# USR_IO_IPMI.net
KiCad netlist of a schematic drawn in Altium Designer
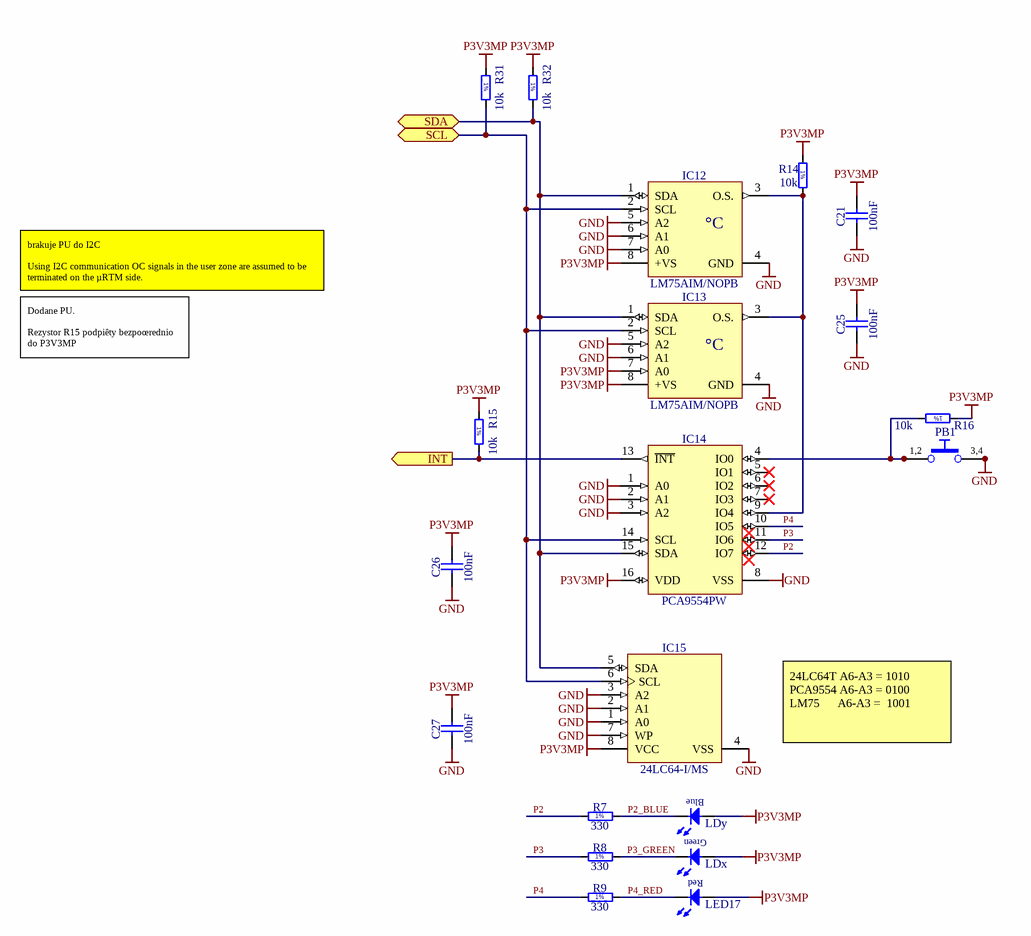
[diagram p0: USR_IO_IPMI.SchDoc]

(export (version "E")
  (design (tool "Eeschema 10.0.6"))
  (components
    (comp (ref "C21")
      (value "100nF")
      (footprint "CAPC1005X55N")
      (description "Non-polarised capacitor")
      (fields
        (field (name "PART NUMBER") "CC0402_100NF_16V_10%_X7R")
        (field (name "VOLTAGE") "16V")
        (field (name "AUTHOR") "CERN DEM JLC")
      )
      (libsource (lib "Capacitors") (part "Capacitor - non polarized"))
    )
    (comp (ref "C25")
      (value "100nF")
      (footprint "CAPC1005X55N")
      (description "Non-polarised capacitor")
      (fields
        (field (name "PART NUMBER") "CC0402_100NF_16V_10%_X7R")
        (field (name "VOLTAGE") "16V")
        (field (name "AUTHOR") "CERN DEM JLC")
      )
      (libsource (lib "Capacitors") (part "Capacitor - non polarized"))
    )
    (comp (ref "C26")
      (value "100nF")
      (footprint "CAPC1005X55N")
      (description "Non-polarised capacitor")
      (fields
        (field (name "PART NUMBER") "CC0402_100NF_16V_10%_X7R")
        (field (name "VOLTAGE") "16V")
        (field (name "AUTHOR") "CERN DEM JLC")
      )
      (libsource (lib "Capacitors") (part "Capacitor - non polarized"))
    )
    (comp (ref "C27")
      (value "100nF")
      (footprint "CAPC1005X55N")
      (description "Non-polarised capacitor")
      (fields
        (field (name "PART NUMBER") "CC0402_100NF_16V_10%_X7R")
        (field (name "VOLTAGE") "16V")
        (field (name "AUTHOR") "CERN DEM JLC")
      )
      (libsource (lib "Capacitors") (part "Capacitor - non polarized"))
    )
    (comp (ref "IC12")
      (value "LM75AIM/NOPB")
      (footprint "SOIC127P600X175-8N")
      (description "Digital Temperature Sensor and Thermal Watchdog with Two-Wire Interface")
      (fields (field (name "MANUFACTURER") "TEXAS INSTRUMENTS") (field (name "AUTHOR") "CERN DEM JLC"))
      (libsource (lib "ICs And Semiconductors") (part "LM75"))
    )
    (comp (ref "IC13")
      (value "LM75AIM/NOPB")
      (footprint "SOIC127P600X175-8N")
      (description "Digital Temperature Sensor and Thermal Watchdog with Two-Wire Interface")
      (fields (field (name "MANUFACTURER") "TEXAS INSTRUMENTS") (field (name "AUTHOR") "CERN DEM JLC"))
      (libsource (lib "ICs And Semiconductors") (part "LM75"))
    )
    (comp (ref "IC14")
      (value "PCA9554PW")
      (footprint "SOP65P640X110-16N")
      (description "8-Bit I2C-Bus and SMBus I/O Port with Interrupt")
      (fields (field (name "MANUFACTURER") "NXP SEMICONDUCTORS") (field (name "AUTHOR") "CERN DEM JLC"))
      (libsource (lib "ICs And Semiconductors") (part "PCA9554PW"))
    )
    (comp (ref "IC15")
      (value "24LC64-I/MS")
      (footprint "SOP65P490X110-8N")
      (description "64K I2C Serial EEPROM")
      (fields (field (name "MANUFACTURER") "MICROCHIP TECHNOLOGY") (field (name "AUTHOR") "CERN DEM JLC"))
      (libsource (lib "ICs And Semiconductors") (part "24LC64-I/MS"))
    )
    (comp (ref "LDx")
      (value "Green")
      (footprint "LED_AVAGO_HSME-C120")
      (description "LED Green 1C 2A")
      (fields
        (field (name "PART NUMBER") "LED_AVAGO_HSME-C120")
        (field (name "MANUFACTURER") "AVAGO TECHNOLOGIES")
        (field (name "AUTHOR") "CERN DEM JMW")
      )
      (libsource (lib "ICs And Semiconductors") (part "LED Green 1C 2A"))
    )
    (comp (ref "LDy")
      (value "Blue")
      (footprint "LED_AVAGO_HSMR-C120")
      (description "LED Blue 1C 2A")
      (fields
        (field (name "PART NUMBER") "LED_AVAGO_HSMR-C120")
        (field (name "MANUFACTURER") "AVAGO TECHNOLOGIES")
        (field (name "AUTHOR") "CERN DEM JLC")
      )
      (libsource (lib "ICs And Semiconductors") (part "LED Blue 1C 2A"))
    )
    (comp (ref "LED17")
      (value "Red")
      (footprint "LEDC1608X80N_RED")
      (description "LED Red 1C 2A")
      (fields
        (field (name "PART NUMBER") "LED_ROHM_SML-311UTT86K")
        (field (name "MANUFACTURER") "ROHM")
        (field (name "AUTHOR") "CERN DEM JLC")
      )
      (libsource (lib "ICs And Semiconductors") (part "LED Red 1C 2A"))
    )
    (comp (ref "PB1")
      (value "Push Button")
      (footprint "SW_C&K_HDT0001")
      (description "Push-Button Switch SPDT")
      (fields
        (field (name "PART NUMBER") "SW_C&K_HDT0001")
        (field (name "MANUFACTURER") "C&K")
        (field (name "AUTHOR") "CERN DEM JLC")
      )
      (libsource (lib "Eletro-mechanical") (part "PB SPST 12NO-34NO"))
    )
    (comp (ref "R7")
      (value "330")
      (footprint "RESC1608X55N")
      (description "Resistor - 1%")
      (fields
        (field (name "PART NUMBER") "R0603_330R_1%_0.1W_100PPM")
        (field (name "POWER") "0.1W")
        (field (name "AUTHOR") "CERN DEM JLC")
      )
      (libsource (lib "Resistors") (part "Resistor - 1%"))
    )
    (comp (ref "R8")
      (value "330")
      (footprint "RESC1608X55N")
      (description "Resistor - 1%")
      (fields
        (field (name "PART NUMBER") "R0603_330R_1%_0.1W_100PPM")
        (field (name "POWER") "0.1W")
        (field (name "AUTHOR") "CERN DEM JLC")
      )
      (libsource (lib "Resistors") (part "Resistor - 1%"))
    )
    (comp (ref "R9")
      (value "330")
      (footprint "RESC1608X55N")
      (description "Resistor - 1%")
      (fields
        (field (name "PART NUMBER") "R0603_330R_1%_0.1W_100PPM")
        (field (name "POWER") "0.1W")
        (field (name "AUTHOR") "CERN DEM JLC")
      )
      (libsource (lib "Resistors") (part "Resistor - 1%"))
    )
    (comp (ref "R14")
      (value "10k")
      (footprint "RESC1005X40N")
      (description "Resistor - 1%")
      (fields
        (field (name "PART NUMBER") "R0402_10K_1%_0.0625W_100PPM")
        (field (name "POWER") "0.0625W")
        (field (name "AUTHOR") "CERN DEM JLC")
      )
      (libsource (lib "Resistors") (part "Resistor - 1%"))
    )
    (comp (ref "R15")
      (value "10k")
      (footprint "RESC1005X40N")
      (description "Resistor - 1%")
      (fields
        (field (name "PART NUMBER") "R0402_10K_1%_0.0625W_100PPM")
        (field (name "POWER") "0.0625W")
        (field (name "AUTHOR") "CERN DEM JLC")
      )
      (libsource (lib "Resistors") (part "Resistor - 1%"))
    )
    (comp (ref "R16")
      (value "10k")
      (footprint "RESC1005X40N")
      (description "Resistor - 1%")
      (fields
        (field (name "PART NUMBER") "R0402_10K_1%_0.0625W_100PPM")
        (field (name "POWER") "0.0625W")
        (field (name "AUTHOR") "CERN DEM JLC")
      )
      (libsource (lib "Resistors") (part "Resistor - 1%"))
    )
    (comp (ref "R31")
      (value "10k")
      (footprint "RESC1005X40N")
      (description "Resistor - 1%")
      (fields
        (field (name "PART NUMBER") "R0402_10K_1%_0.0625W_100PPM")
        (field (name "POWER") "0.0625W")
        (field (name "AUTHOR") "CERN DEM JLC")
      )
      (libsource (lib "Resistors") (part "Resistor - 1%"))
    )
    (comp (ref "R32")
      (value "10k")
      (footprint "RESC1005X40N")
      (description "Resistor - 1%")
      (fields
        (field (name "PART NUMBER") "R0402_10K_1%_0.0625W_100PPM")
        (field (name "POWER") "0.0625W")
        (field (name "AUTHOR") "CERN DEM JLC")
      )
      (libsource (lib "Resistors") (part "Resistor - 1%"))
    )
  )
  (nets
    (net (code "1") (name "/INT") (class "Default")
      (node (ref "IC14") (pin "13") (pinfunction "~{INT}_13") (pintype "output"))
      (node (ref "R15") (pin "2") (pinfunction "2_2") (pintype "passive"))
    )
    (net (code "2") (name "/P2") (class "Default")
      (node (ref "IC14") (pin "12") (pinfunction "IO7_12") (pintype "bidirectional"))
      (node (ref "R7") (pin "1") (pinfunction "1_1") (pintype "passive"))
    )
    (net (code "3") (name "/P2_BLUE") (class "Default")
      (node (ref "LDy") (pin "1") (pinfunction "C_1") (pintype "passive"))
      (node (ref "R7") (pin "2") (pinfunction "2_2") (pintype "passive"))
    )
    (net (code "4") (name "/P3") (class "Default")
      (node (ref "IC14") (pin "11") (pinfunction "IO6_11") (pintype "bidirectional"))
      (node (ref "R8") (pin "1") (pinfunction "1_1") (pintype "passive"))
    )
    (net (code "5") (name "/P3_GREEN") (class "Default")
      (node (ref "LDx") (pin "1") (pinfunction "C_1") (pintype "passive"))
      (node (ref "R8") (pin "2") (pinfunction "2_2") (pintype "passive"))
    )
    (net (code "6") (name "/P4") (class "Default")
      (node (ref "IC14") (pin "10") (pinfunction "IO5_10") (pintype "bidirectional"))
      (node (ref "R9") (pin "1") (pinfunction "1_1") (pintype "passive"))
    )
    (net (code "7") (name "/P4_RED") (class "Default")
      (node (ref "LED17") (pin "1") (pinfunction "C_1") (pintype "passive"))
      (node (ref "R9") (pin "2") (pinfunction "2_2") (pintype "passive"))
    )
    (net (code "8") (name "/SCL") (class "Default")
      (node (ref "IC12") (pin "2") (pinfunction "SCL_2") (pintype "input"))
      (node (ref "IC13") (pin "2") (pinfunction "SCL_2") (pintype "input"))
      (node (ref "IC14") (pin "14") (pinfunction "SCL_14") (pintype "input"))
      (node (ref "IC15") (pin "6") (pinfunction "SCL_6") (pintype "input"))
      (node (ref "R31") (pin "2") (pinfunction "2_2") (pintype "passive"))
    )
    (net (code "9") (name "/SDA") (class "Default")
      (node (ref "IC12") (pin "1") (pinfunction "SDA_1") (pintype "bidirectional"))
      (node (ref "IC13") (pin "1") (pinfunction "SDA_1") (pintype "bidirectional"))
      (node (ref "IC14") (pin "15") (pinfunction "SDA_15") (pintype "bidirectional"))
      (node (ref "IC15") (pin "5") (pinfunction "SDA_5") (pintype "bidirectional"))
      (node (ref "R32") (pin "2") (pinfunction "2_2") (pintype "passive"))
    )
    (net (code "10") (name "GND") (class "Default")
      (node (ref "C21") (pin "2") (pinfunction "2_2") (pintype "passive"))
      (node (ref "C25") (pin "2") (pinfunction "2_2") (pintype "passive"))
      (node (ref "C26") (pin "2") (pinfunction "2_2") (pintype "passive"))
      (node (ref "C27") (pin "2") (pinfunction "2_2") (pintype "passive"))
      (node (ref "IC12") (pin "4") (pinfunction "GND_4") (pintype "power_in"))
      (node (ref "IC12") (pin "5") (pinfunction "A2_5") (pintype "input"))
      (node (ref "IC12") (pin "6") (pinfunction "A1_6") (pintype "input"))
      (node (ref "IC12") (pin "7") (pinfunction "A0_7") (pintype "input"))
      (node (ref "IC13") (pin "4") (pinfunction "GND_4") (pintype "power_in"))
      (node (ref "IC13") (pin "5") (pinfunction "A2_5") (pintype "input"))
      (node (ref "IC13") (pin "6") (pinfunction "A1_6") (pintype "input"))
      (node (ref "IC14") (pin "1") (pinfunction "A0_1") (pintype "input"))
      (node (ref "IC14") (pin "2") (pinfunction "A1_2") (pintype "input"))
      (node (ref "IC14") (pin "3") (pinfunction "A2_3") (pintype "input"))
      (node (ref "IC14") (pin "8") (pinfunction "VSS_8") (pintype "power_in"))
      (node (ref "IC15") (pin "1") (pinfunction "A0_1") (pintype "input"))
      (node (ref "IC15") (pin "2") (pinfunction "A1_2") (pintype "input"))
      (node (ref "IC15") (pin "3") (pinfunction "A2_3") (pintype "input"))
      (node (ref "IC15") (pin "4") (pinfunction "VSS_4") (pintype "power_in"))
      (node (ref "IC15") (pin "7") (pinfunction "WP_7") (pintype "input"))
      (node (ref "PB1") (pin "3") (pinfunction "3_3") (pintype "passive"))
      (node (ref "PB1") (pin "4") (pinfunction "4_4") (pintype "passive"))
    )
    (net (code "11") (name "Net-(IC12-O.S.)") (class "Default")
      (node (ref "IC12") (pin "3") (pinfunction "O.S._3") (pintype "output"))
      (node (ref "IC13") (pin "3") (pinfunction "O.S._3") (pintype "output"))
      (node (ref "IC14") (pin "9") (pinfunction "IO4_9") (pintype "bidirectional"))
      (node (ref "R14") (pin "2") (pinfunction "2_2") (pintype "passive"))
    )
    (net (code "12") (name "Net-(IC14-IO0)") (class "Default")
      (node (ref "IC14") (pin "4") (pinfunction "IO0_4") (pintype "bidirectional"))
      (node (ref "PB1") (pin "1") (pinfunction "1_1") (pintype "passive"))
      (node (ref "PB1") (pin "2") (pinfunction "2_2") (pintype "passive"))
      (node (ref "R16") (pin "2") (pinfunction "2_2") (pintype "passive"))
    )
    (net (code "13") (name "P3V3MP") (class "Default")
      (node (ref "C21") (pin "1") (pinfunction "1_1") (pintype "passive"))
      (node (ref "C25") (pin "1") (pinfunction "1_1") (pintype "passive"))
      (node (ref "C26") (pin "1") (pinfunction "1_1") (pintype "passive"))
      (node (ref "C27") (pin "1") (pinfunction "1_1") (pintype "passive"))
      (node (ref "IC12") (pin "8") (pinfunction "+VS_8") (pintype "power_in"))
      (node (ref "IC13") (pin "7") (pinfunction "A0_7") (pintype "input"))
      (node (ref "IC13") (pin "8") (pinfunction "+VS_8") (pintype "power_in"))
      (node (ref "IC14") (pin "16") (pinfunction "VDD_16") (pintype "bidirectional"))
      (node (ref "IC15") (pin "8") (pinfunction "VCC_8") (pintype "power_in"))
      (node (ref "LDx") (pin "2") (pinfunction "A_2") (pintype "passive"))
      (node (ref "LDy") (pin "2") (pinfunction "A_2") (pintype "passive"))
      (node (ref "LED17") (pin "2") (pinfunction "A_2") (pintype "passive"))
      (node (ref "R14") (pin "1") (pinfunction "1_1") (pintype "passive"))
      (node (ref "R15") (pin "1") (pinfunction "1_1") (pintype "passive"))
      (node (ref "R16") (pin "1") (pinfunction "1_1") (pintype "passive"))
      (node (ref "R31") (pin "1") (pinfunction "1_1") (pintype "passive"))
      (node (ref "R32") (pin "1") (pinfunction "1_1") (pintype "passive"))
    )
    (net (code "14") (name "unconnected-(IC14-IO1-Pad5)") (class "Default")
      (node (ref "IC14") (pin "5") (pinfunction "IO1_5") (pintype "bidirectional+no_connect"))
    )
    (net (code "15") (name "unconnected-(IC14-IO2-Pad6)") (class "Default")
      (node (ref "IC14") (pin "6") (pinfunction "IO2_6") (pintype "bidirectional+no_connect"))
    )
    (net (code "16") (name "unconnected-(IC14-IO3-Pad7)") (class "Default")
      (node (ref "IC14") (pin "7") (pinfunction "IO3_7") (pintype "bidirectional+no_connect"))
    )
  )
)
